# 6-CURRENT_CHECK.net
KiCad netlist of a schematic drawn in Altium Designer
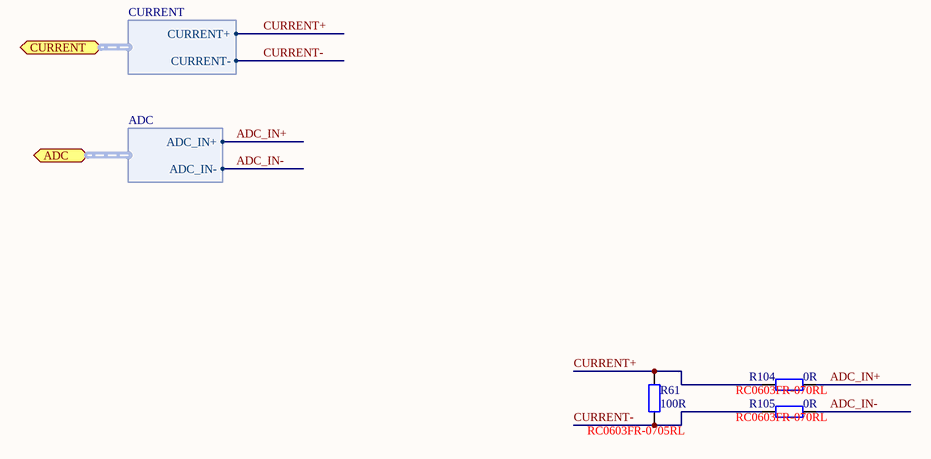
[diagram p0: 6-CURRENT_CHECK.SchDoc]

(export (version "E")
  (design (tool "Eeschema 10.0.6"))
  (components
    (comp (ref "R61")
      (value "100R")
      (footprint "CC0603")
      (description "Resistor")
      (fields (field (name "TYPE NO.") "RC0603FR-0705RL"))
      (libsource (lib "") (part "Res2_1"))
    )
    (comp (ref "R104")
      (value "0R")
      (footprint "CC0603")
      (description "Resistor")
      (fields (field (name "TYPE NO.") "RC0603FR-070RL"))
      (libsource (lib "Miscellaneous Devices") (part "Res2"))
    )
    (comp (ref "R105")
      (value "0R")
      (footprint "CC0603")
      (description "Resistor")
      (fields (field (name "TYPE NO.") "RC0603FR-070RL"))
      (libsource (lib "Miscellaneous Devices") (part "Res2"))
    )
  )
  (nets
    (net (code "3") (name "/ADC_IN+") (class "Default")
      (node (ref "R104") (pin "1") (pinfunction "1_1") (pintype "passive"))
    )
    (net (code "4") (name "/ADC_IN-") (class "Default")
      (node (ref "R105") (pin "1") (pinfunction "1_1") (pintype "passive"))
    )
    (net (code "5") (name "/CURRENT+") (class "Default")
      (node (ref "R104") (pin "2") (pinfunction "2_2") (pintype "passive"))
      (node (ref "R61") (pin "1") (pinfunction "1_1") (pintype "passive"))
    )
    (net (code "6") (name "/CURRENT-") (class "Default")
      (node (ref "R105") (pin "2") (pinfunction "2_2") (pintype "passive"))
      (node (ref "R61") (pin "2") (pinfunction "2_2") (pintype "passive"))
    )
  )
)
